# SCH_Line_Following_Robot_2023-12-15.net
KiCad netlist of a schematic drawn in EasyEDA
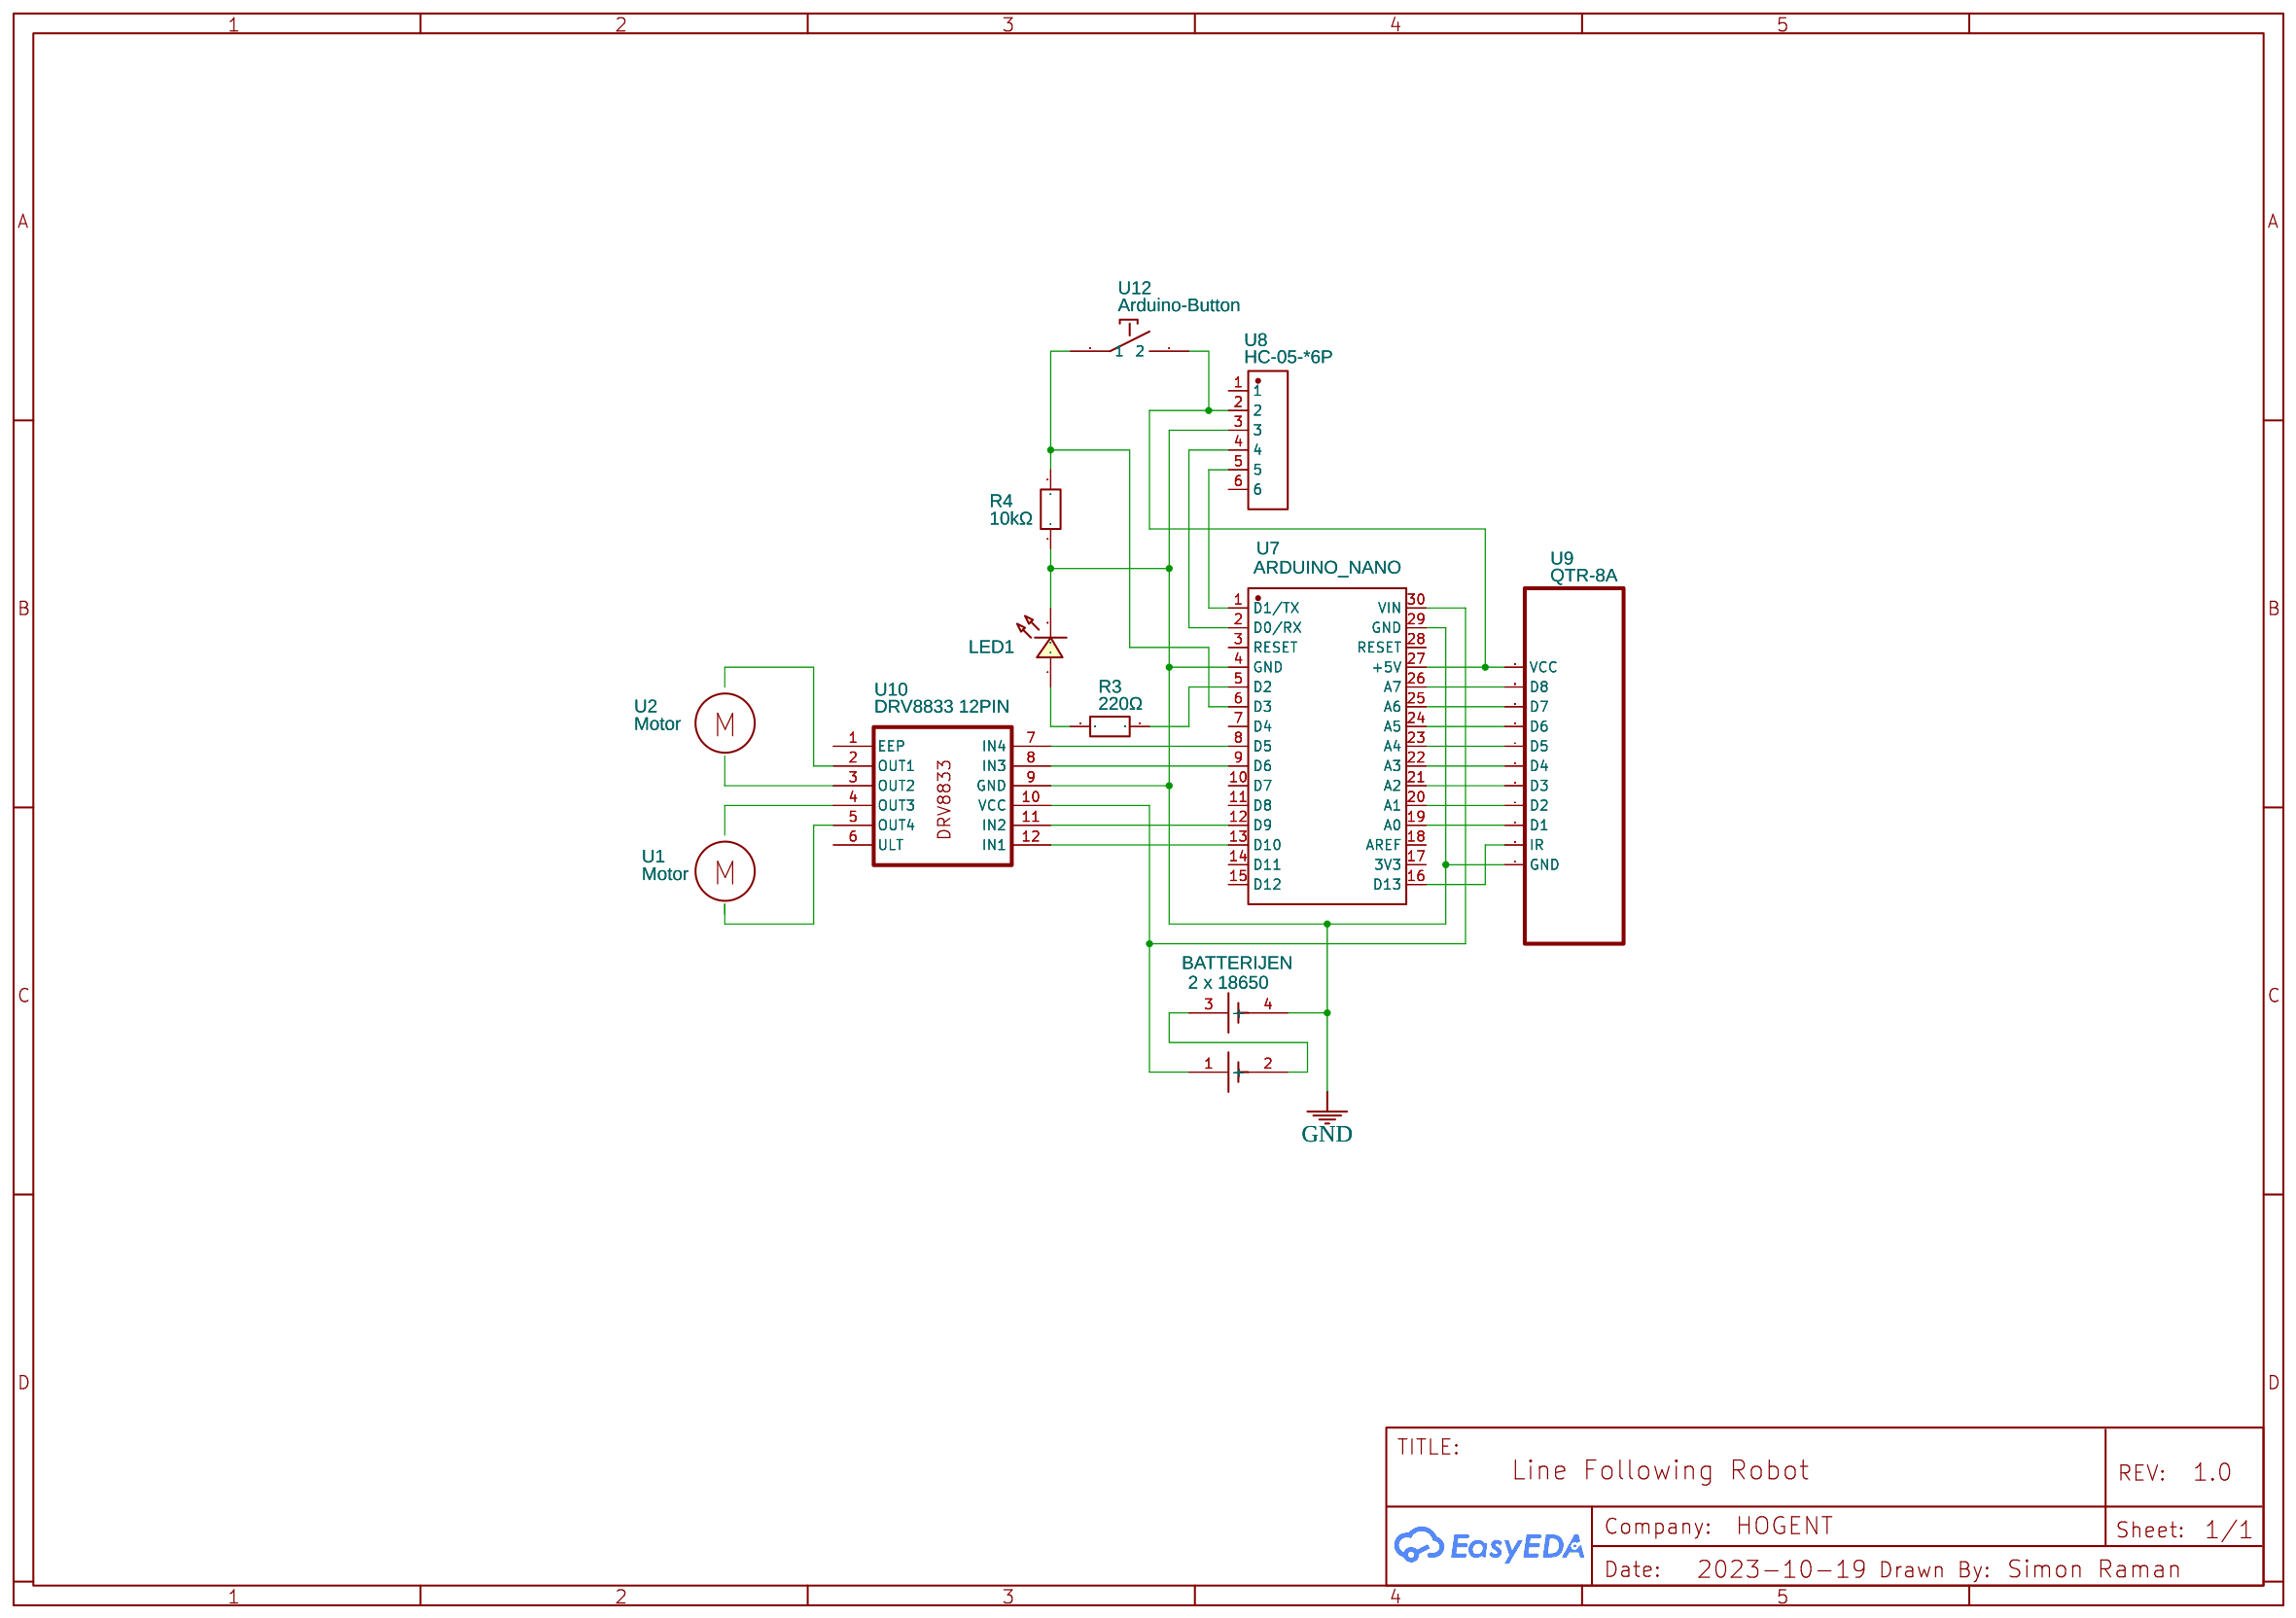
[diagram p0: schematic sheet]

(export (version "E")
  (design (tool "Eeschema 10.0.6"))
  (components
    (comp (ref "BATTERIJEN")
      (value "2 x 18650")
      (fields (field (name "Manufacturer Part") "BAT_X2_18650") (field (name "Manufacturer") "Dex"))
      (libsource (lib "") (part "BAT_X2_18650"))
    )
    (comp (ref "LED1")
      (value "LED-TH-5mm_R")
      (fields
        (field (name "Manufacturer Part") "333-2SURD/S530-A3")
        (field (name "Manufacturer") "EVERLIGHT(台湾亿光)")
      )
      (libsource (lib "") (part "LED-TH-5mm_R"))
    )
    (comp (ref "R3")
      (value "220Ω")
      (libsource (lib "") (part "AXIAL RESISTOR 220 OHM - TH_BD2.3-L6.0-P10.00-D0.4"))
    )
    (comp (ref "R4")
      (value "10kΩ")
      (libsource (lib "") (part "AXIAL RESISTOR 220 OHM - TH_BD2.3-L6.0-P10.00-D0.4_1"))
    )
    (comp (ref "U1") (value "Motor") (libsource (lib "") (part "Motor")))
    (comp (ref "U2") (value "Motor") (libsource (lib "") (part "Motor")))
    (comp (ref "U7") (value "ARDUINO_NANO") (libsource (lib "") (part "ARDUINO_NANO")))
    (comp (ref "U8")
      (value "HC-05-*6P")
      (fields (field (name "Manufacturer Part") "HC-05_排母*6P"))
      (libsource (lib "") (part "HC-05-*6P"))
    )
    (comp (ref "U9") (value "QTR-8A") (libsource (lib "") (part "QTR-8A")))
    (comp (ref "U10") (value "DRV8833 12PIN") (libsource (lib "") (part "DRV8833 12PIN")))
    (comp (ref "U12")
      (value "Arduino-Button")
      (fields (field (name "Manufacturer Part") "SW100664"))
      (libsource (lib "") (part "Arduino-Button"))
    )
  )
  (nets
    (net (code "1") (name "GND") (class "Default")
      (node (ref "BATTERIJEN") (pin "4") (pinfunction "-_4") (pintype "unspecified"))
      (node (ref "LED1") (pin "2") (pinfunction "2_2") (pintype "unspecified"))
      (node (ref "R4") (pin "1") (pinfunction "1_1") (pintype "unspecified"))
      (node (ref "U10") (pin "9") (pinfunction "GND_9") (pintype "unspecified"))
      (node (ref "U7") (pin "29") (pinfunction "GND_29") (pintype "unspecified"))
      (node (ref "U7") (pin "4") (pinfunction "GND_4") (pintype "unspecified"))
      (node (ref "U8") (pin "3") (pinfunction "3_3") (pintype "unspecified"))
      (node (ref "U9") (pin "1") (pinfunction "GND_1") (pintype "unspecified"))
    )
    (net (code "2") (name "Net-(BATTERIJEN-+-Pad3)") (class "Default")
      (node (ref "BATTERIJEN") (pin "2") (pinfunction "-_2") (pintype "unspecified"))
      (node (ref "BATTERIJEN") (pin "3") (pinfunction "+_3") (pintype "unspecified"))
    )
    (net (code "3") (name "Net-(LED1-Pad1)") (class "Default")
      (node (ref "LED1") (pin "1") (pinfunction "1_1") (pintype "unspecified"))
      (node (ref "R3") (pin "1") (pinfunction "1_1") (pintype "unspecified"))
    )
    (net (code "4") (name "Net-(U7-+5V)") (class "Default")
      (node (ref "U12") (pin "2") (pinfunction "2_2") (pintype "unspecified"))
      (node (ref "U7") (pin "27") (pinfunction "+5V_27") (pintype "unspecified"))
      (node (ref "U8") (pin "2") (pinfunction "2_2") (pintype "unspecified"))
      (node (ref "U9") (pin "11") (pinfunction "VCC_11") (pintype "unspecified"))
    )
    (net (code "5") (name "Net-(U7-A0)") (class "Default")
      (node (ref "U7") (pin "19") (pinfunction "A0_19") (pintype "unspecified"))
      (node (ref "U9") (pin "3") (pinfunction "D1_3") (pintype "unspecified"))
    )
    (net (code "6") (name "Net-(U7-A1)") (class "Default")
      (node (ref "U7") (pin "20") (pinfunction "A1_20") (pintype "unspecified"))
      (node (ref "U9") (pin "4") (pinfunction "D2_4") (pintype "unspecified"))
    )
    (net (code "7") (name "Net-(U7-A2)") (class "Default")
      (node (ref "U7") (pin "21") (pinfunction "A2_21") (pintype "unspecified"))
      (node (ref "U9") (pin "5") (pinfunction "D3_5") (pintype "unspecified"))
    )
    (net (code "8") (name "Net-(U7-A3)") (class "Default")
      (node (ref "U7") (pin "22") (pinfunction "A3_22") (pintype "unspecified"))
      (node (ref "U9") (pin "6") (pinfunction "D4_6") (pintype "unspecified"))
    )
    (net (code "9") (name "Net-(U7-A4)") (class "Default")
      (node (ref "U7") (pin "23") (pinfunction "A4_23") (pintype "unspecified"))
      (node (ref "U9") (pin "7") (pinfunction "D5_7") (pintype "unspecified"))
    )
    (net (code "10") (name "Net-(U7-A5)") (class "Default")
      (node (ref "U7") (pin "24") (pinfunction "A5_24") (pintype "unspecified"))
      (node (ref "U9") (pin "8") (pinfunction "D6_8") (pintype "unspecified"))
    )
    (net (code "11") (name "Net-(U7-A6)") (class "Default")
      (node (ref "U7") (pin "25") (pinfunction "A6_25") (pintype "unspecified"))
      (node (ref "U9") (pin "9") (pinfunction "D7_9") (pintype "unspecified"))
    )
    (net (code "12") (name "Net-(U7-A7)") (class "Default")
      (node (ref "U7") (pin "26") (pinfunction "A7_26") (pintype "unspecified"))
      (node (ref "U9") (pin "10") (pinfunction "D8_10") (pintype "unspecified"))
    )
    (net (code "13") (name "Net-(U7-D0{slash}RX)") (class "Default")
      (node (ref "U7") (pin "2") (pinfunction "D0/RX_2") (pintype "unspecified"))
      (node (ref "U8") (pin "4") (pinfunction "4_4") (pintype "unspecified"))
    )
    (net (code "14") (name "Net-(U7-D1{slash}TX)") (class "Default")
      (node (ref "U7") (pin "1") (pinfunction "D1/TX_1") (pintype "unspecified"))
      (node (ref "U8") (pin "5") (pinfunction "5_5") (pintype "unspecified"))
    )
    (net (code "15") (name "Net-(U7-D2)") (class "Default")
      (node (ref "R3") (pin "2") (pinfunction "2_2") (pintype "unspecified"))
      (node (ref "U7") (pin "5") (pinfunction "D2_5") (pintype "unspecified"))
    )
    (net (code "16") (name "Net-(U7-D3)") (class "Default")
      (node (ref "R4") (pin "2") (pinfunction "2_2") (pintype "unspecified"))
      (node (ref "U12") (pin "1") (pinfunction "1_1") (pintype "unspecified"))
      (node (ref "U7") (pin "6") (pinfunction "D3_6") (pintype "unspecified"))
    )
    (net (code "17") (name "Net-(U7-D13)") (class "Default")
      (node (ref "U7") (pin "16") (pinfunction "D13_16") (pintype "unspecified"))
      (node (ref "U9") (pin "2") (pinfunction "IR_2") (pintype "unspecified"))
    )
    (net (code "18") (name "Net-(U10-IN1)") (class "Default")
      (node (ref "U10") (pin "12") (pinfunction "IN1_12") (pintype "unspecified"))
      (node (ref "U7") (pin "13") (pinfunction "D10_13") (pintype "unspecified"))
    )
    (net (code "19") (name "Net-(U10-IN2)") (class "Default")
      (node (ref "U10") (pin "11") (pinfunction "IN2_11") (pintype "unspecified"))
      (node (ref "U7") (pin "12") (pinfunction "D9_12") (pintype "unspecified"))
    )
    (net (code "20") (name "Net-(U10-IN3)") (class "Default")
      (node (ref "U10") (pin "8") (pinfunction "IN3_8") (pintype "unspecified"))
      (node (ref "U7") (pin "9") (pinfunction "D6_9") (pintype "unspecified"))
    )
    (net (code "21") (name "Net-(U10-IN4)") (class "Default")
      (node (ref "U10") (pin "7") (pinfunction "IN4_7") (pintype "unspecified"))
      (node (ref "U7") (pin "8") (pinfunction "D5_8") (pintype "unspecified"))
    )
    (net (code "22") (name "Net-(U10-VCC)") (class "Default")
      (node (ref "BATTERIJEN") (pin "1") (pinfunction "+_1") (pintype "unspecified"))
      (node (ref "U10") (pin "10") (pinfunction "VCC_10") (pintype "unspecified"))
      (node (ref "U7") (pin "30") (pinfunction "VIN_30") (pintype "unspecified"))
    )
    (net (code "23") (name "unconnected-(U7-3V3-Pad17)") (class "Default")
      (node (ref "U7") (pin "17") (pinfunction "3V3_17") (pintype "unspecified"))
    )
    (net (code "24") (name "unconnected-(U7-AREF-Pad18)") (class "Default")
      (node (ref "U7") (pin "18") (pinfunction "AREF_18") (pintype "unspecified"))
    )
    (net (code "25") (name "unconnected-(U7-D4-Pad7)") (class "Default")
      (node (ref "U7") (pin "7") (pinfunction "D4_7") (pintype "unspecified"))
    )
    (net (code "26") (name "unconnected-(U7-D7-Pad10)") (class "Default")
      (node (ref "U7") (pin "10") (pinfunction "D7_10") (pintype "unspecified"))
    )
    (net (code "27") (name "unconnected-(U7-D8-Pad11)") (class "Default")
      (node (ref "U7") (pin "11") (pinfunction "D8_11") (pintype "unspecified"))
    )
    (net (code "28") (name "unconnected-(U7-D11-Pad14)") (class "Default")
      (node (ref "U7") (pin "14") (pinfunction "D11_14") (pintype "unspecified"))
    )
    (net (code "29") (name "unconnected-(U7-D12-Pad15)") (class "Default")
      (node (ref "U7") (pin "15") (pinfunction "D12_15") (pintype "unspecified"))
    )
    (net (code "30") (name "unconnected-(U7-RESET-Pad3)") (class "Default")
      (node (ref "U7") (pin "3") (pinfunction "RESET_3") (pintype "unspecified"))
    )
    (net (code "31") (name "unconnected-(U7-RESET-Pad28)") (class "Default")
      (node (ref "U7") (pin "28") (pinfunction "RESET_28") (pintype "unspecified"))
    )
    (net (code "32") (name "unconnected-(U8-Pad1)") (class "Default")
      (node (ref "U8") (pin "1") (pinfunction "1_1") (pintype "unspecified"))
    )
    (net (code "33") (name "unconnected-(U8-Pad6)") (class "Default")
      (node (ref "U8") (pin "6") (pinfunction "6_6") (pintype "unspecified"))
    )
    (net (code "34") (name "unconnected-(U10-EEP-Pad1)") (class "Default")
      (node (ref "U10") (pin "1") (pinfunction "EEP_1") (pintype "unspecified"))
    )
    (net (code "35") (name "unconnected-(U10-OUT1-Pad2)") (class "Default")
      (node (ref "U10") (pin "2") (pinfunction "OUT1_2") (pintype "unspecified"))
    )
    (net (code "36") (name "unconnected-(U10-OUT2-Pad3)") (class "Default")
      (node (ref "U10") (pin "3") (pinfunction "OUT2_3") (pintype "unspecified"))
    )
    (net (code "37") (name "unconnected-(U10-OUT3-Pad4)") (class "Default")
      (node (ref "U10") (pin "4") (pinfunction "OUT3_4") (pintype "unspecified"))
    )
    (net (code "38") (name "unconnected-(U10-OUT4-Pad5)") (class "Default")
      (node (ref "U10") (pin "5") (pinfunction "OUT4_5") (pintype "unspecified"))
    )
    (net (code "39") (name "unconnected-(U10-ULT-Pad6)") (class "Default")
      (node (ref "U10") (pin "6") (pinfunction "ULT_6") (pintype "unspecified"))
    )
  )
)
